# STM32F103VET6.net
KiCad netlist of a schematic drawn in Altium Designer
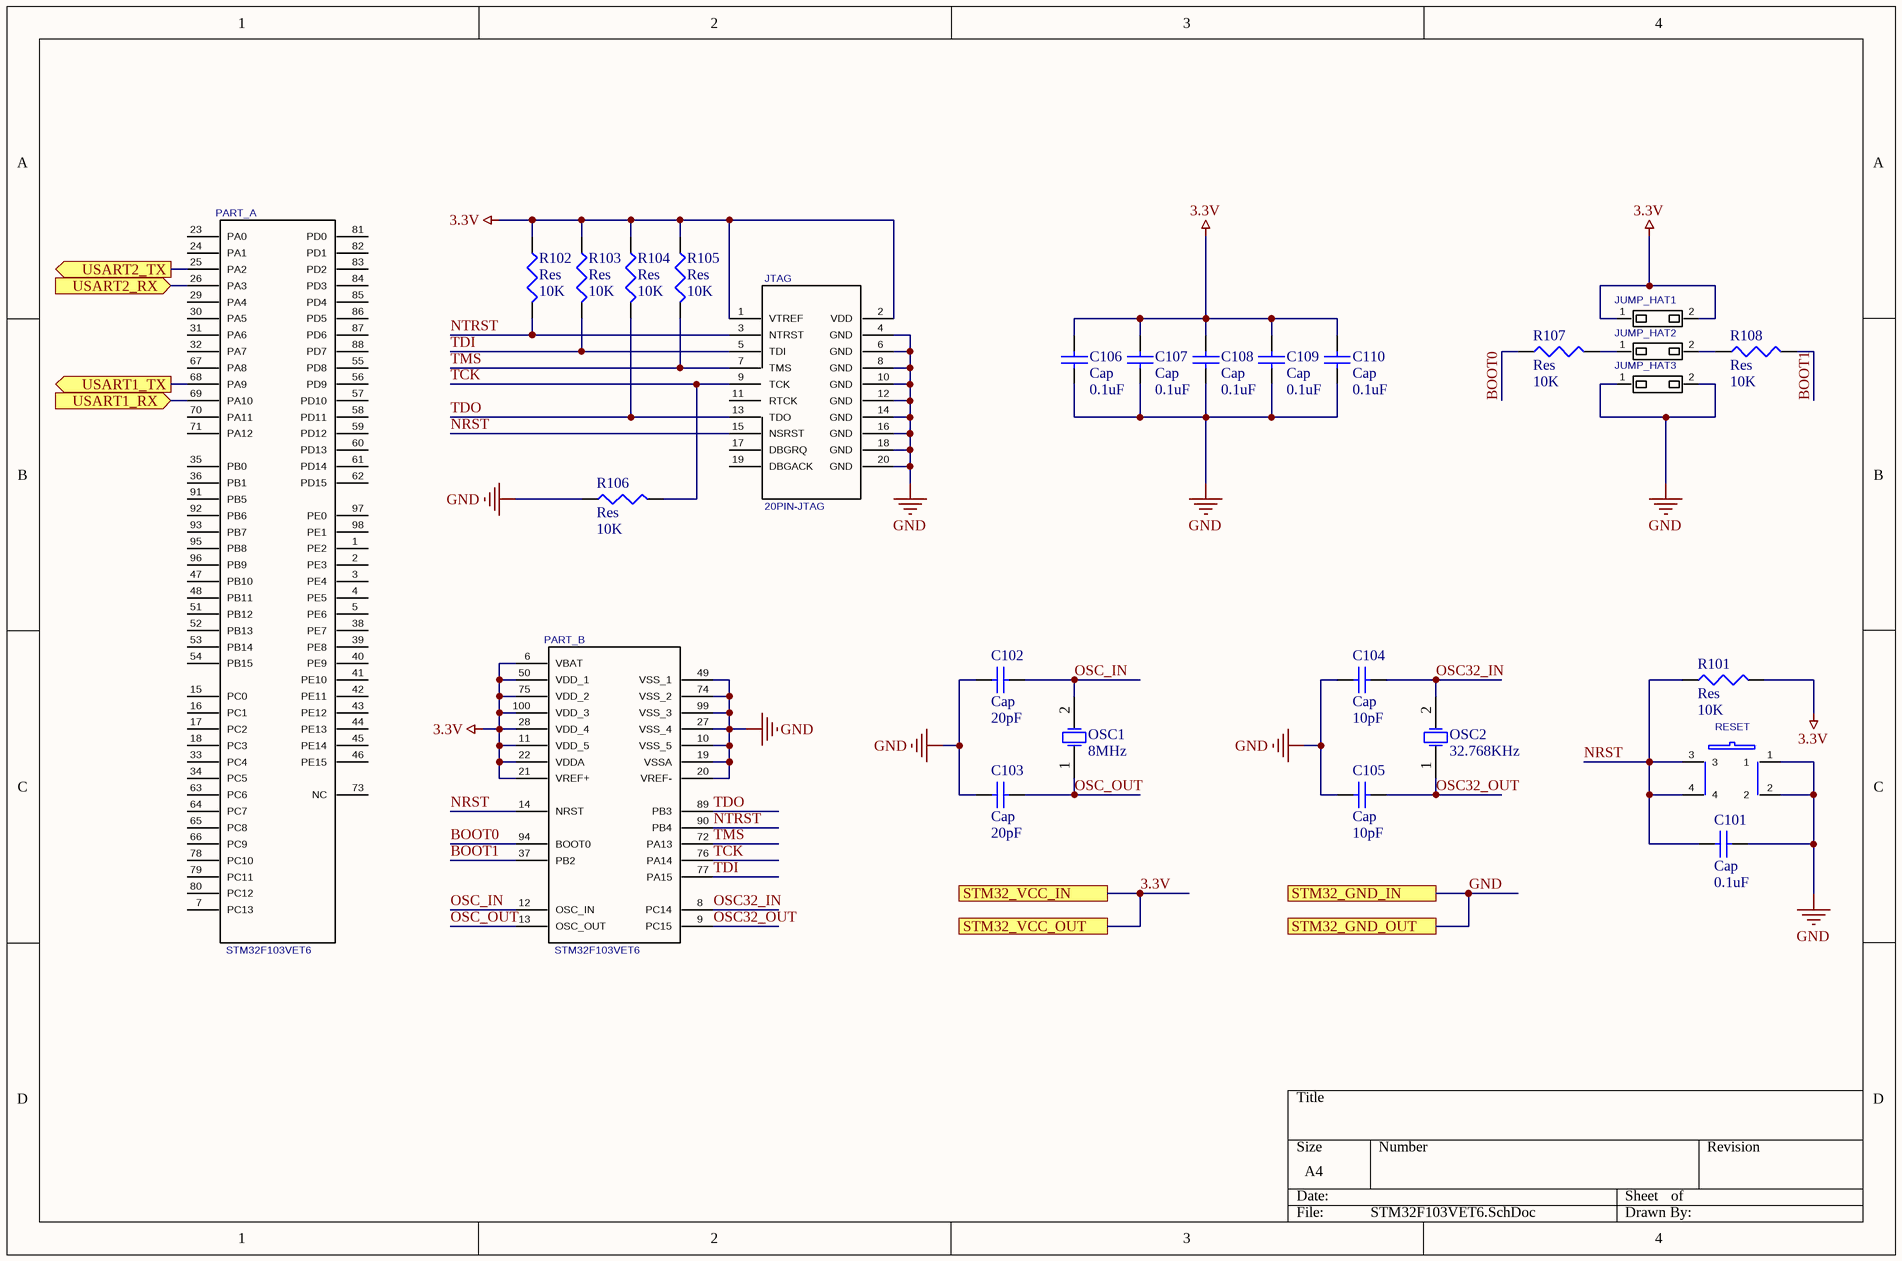
[diagram p0: STM32F103VET6.SchDoc]

(export (version "E")
  (design (tool "Eeschema 10.0.6"))
  (components
    (comp (ref "C101")
      (value "Cap")
      (footprint "RAD-0.3")
      (description "Capacitor")
      (fields (field (name "ALTIUM_VALUE") "0.1uF") (field (name "PUBLISHER") "Altium Limited"))
      (libsource (lib "Miscellaneous Devices") (part "Cap"))
    )
    (comp (ref "C102")
      (value "Cap")
      (footprint "RAD-0.3")
      (description "Capacitor")
      (fields (field (name "ALTIUM_VALUE") "20pF") (field (name "PUBLISHER") "Altium Limited"))
      (libsource (lib "Miscellaneous Devices") (part "Cap"))
    )
    (comp (ref "C103")
      (value "Cap")
      (footprint "RAD-0.3")
      (description "Capacitor")
      (fields (field (name "ALTIUM_VALUE") "20pF") (field (name "PUBLISHER") "Altium Limited"))
      (libsource (lib "Miscellaneous Devices") (part "Cap"))
    )
    (comp (ref "C104")
      (value "Cap")
      (footprint "RAD-0.3")
      (description "Capacitor")
      (fields (field (name "ALTIUM_VALUE") "10pF") (field (name "PUBLISHER") "Altium Limited"))
      (libsource (lib "Miscellaneous Devices") (part "Cap"))
    )
    (comp (ref "C105")
      (value "Cap")
      (footprint "RAD-0.3")
      (description "Capacitor")
      (fields (field (name "ALTIUM_VALUE") "10pF") (field (name "PUBLISHER") "Altium Limited"))
      (libsource (lib "Miscellaneous Devices") (part "Cap"))
    )
    (comp (ref "C106")
      (value "Cap")
      (footprint "RAD-0.3")
      (description "Capacitor")
      (fields (field (name "ALTIUM_VALUE") "0.1uF") (field (name "PUBLISHER") "Altium Limited"))
      (libsource (lib "Miscellaneous Devices") (part "Cap"))
    )
    (comp (ref "C107")
      (value "Cap")
      (footprint "RAD-0.3")
      (description "Capacitor")
      (fields (field (name "ALTIUM_VALUE") "0.1uF") (field (name "PUBLISHER") "Altium Limited"))
      (libsource (lib "Miscellaneous Devices") (part "Cap"))
    )
    (comp (ref "C108")
      (value "Cap")
      (footprint "RAD-0.3")
      (description "Capacitor")
      (fields (field (name "ALTIUM_VALUE") "0.1uF") (field (name "PUBLISHER") "Altium Limited"))
      (libsource (lib "Miscellaneous Devices") (part "Cap"))
    )
    (comp (ref "C109")
      (value "Cap")
      (footprint "RAD-0.3")
      (description "Capacitor")
      (fields (field (name "ALTIUM_VALUE") "0.1uF") (field (name "PUBLISHER") "Altium Limited"))
      (libsource (lib "Miscellaneous Devices") (part "Cap"))
    )
    (comp (ref "C110")
      (value "Cap")
      (footprint "RAD-0.3")
      (description "Capacitor")
      (fields (field (name "ALTIUM_VALUE") "0.1uF") (field (name "PUBLISHER") "Altium Limited"))
      (libsource (lib "Miscellaneous Devices") (part "Cap"))
    )
    (comp (ref "JTAG")
      (value "20PIN-JTAG")
      (footprint "FC20H")
      (description "20pin JTAG")
      (libsource (lib "MINI-V3") (part "20PIN-JTAG"))
    )
    (comp (ref "JUMP_HAT1")
      (value "1X2PIN_SMD")
      (footprint "1X2PIN_SMD")
      (libsource (lib "MINI-V3") (part "1X2PIN_SMD"))
    )
    (comp (ref "JUMP_HAT2")
      (value "1X2PIN_SMD")
      (footprint "1X2PIN_SMD")
      (libsource (lib "MINI-V3") (part "1X2PIN_SMD"))
    )
    (comp (ref "JUMP_HAT3")
      (value "1X2PIN_SMD")
      (footprint "1X2PIN_SMD")
      (libsource (lib "MINI-V3") (part "1X2PIN_SMD"))
    )
    (comp (ref "OSC1")
      (value "8MHz")
      (footprint "R38")
      (description "Crystal Oscillator")
      (fields (field (name "PUBLISHER") "Altium Limited"))
      (libsource (lib "Miscellaneous Devices") (part "XTAL"))
    )
    (comp (ref "OSC2")
      (value "32.768KHz")
      (footprint "R38")
      (description "Crystal Oscillator")
      (fields (field (name "PUBLISHER") "Altium Limited"))
      (libsource (lib "Miscellaneous Devices") (part "XTAL"))
    )
    (comp (ref "PART_")
      (value "STM32F103VET6")
      (footprint "STM32F103VET6-LQFP")
      (libsource (lib "MINI-V3") (part "STM32F103VET6"))
    )
    (comp (ref "R101")
      (value "Res")
      (footprint "J1-0603")
      (description "Resistor")
      (fields (field (name "ALTIUM_VALUE") "10K") (field (name "PUBLISHER") "Altium Limited"))
      (libsource (lib "Miscellaneous Devices") (part "Res3"))
    )
    (comp (ref "R102")
      (value "Res")
      (footprint "J1-0603")
      (description "Resistor")
      (fields (field (name "ALTIUM_VALUE") "10K") (field (name "PUBLISHER") "Altium Limited"))
      (libsource (lib "Miscellaneous Devices") (part "Res3"))
    )
    (comp (ref "R103")
      (value "Res")
      (footprint "J1-0603")
      (description "Resistor")
      (fields (field (name "ALTIUM_VALUE") "10K") (field (name "PUBLISHER") "Altium Limited"))
      (libsource (lib "Miscellaneous Devices") (part "Res3"))
    )
    (comp (ref "R104")
      (value "Res")
      (footprint "J1-0603")
      (description "Resistor")
      (fields (field (name "ALTIUM_VALUE") "10K") (field (name "PUBLISHER") "Altium Limited"))
      (libsource (lib "Miscellaneous Devices") (part "Res3"))
    )
    (comp (ref "R105")
      (value "Res")
      (footprint "J1-0603")
      (description "Resistor")
      (fields (field (name "ALTIUM_VALUE") "10K") (field (name "PUBLISHER") "Altium Limited"))
      (libsource (lib "Miscellaneous Devices") (part "Res3"))
    )
    (comp (ref "R106")
      (value "Res")
      (footprint "J1-0603")
      (description "Resistor")
      (fields (field (name "ALTIUM_VALUE") "10K") (field (name "PUBLISHER") "Altium Limited"))
      (libsource (lib "Miscellaneous Devices") (part "Res3"))
    )
    (comp (ref "R107")
      (value "Res")
      (footprint "J1-0603")
      (description "Resistor")
      (fields (field (name "ALTIUM_VALUE") "10K") (field (name "PUBLISHER") "Altium Limited"))
      (libsource (lib "Miscellaneous Devices") (part "Res3"))
    )
    (comp (ref "R108")
      (value "Res")
      (footprint "J1-0603")
      (description "Resistor")
      (fields (field (name "ALTIUM_VALUE") "10K") (field (name "PUBLISHER") "Altium Limited"))
      (libsource (lib "Miscellaneous Devices") (part "Res3"))
    )
    (comp (ref "RESET") (value "KEY") (footprint "SW6.2/6.2-SMD") (libsource (lib "MINI-V3") (part "KEY")))
  )
  (nets
    (net (code "1") (name "/BOOT0") (class "Default")
      (node (ref "PART_") (pin "94") (pinfunction "BOOT0_94") (pintype "passive"))
      (node (ref "R107") (pin "1") (pinfunction "1_1") (pintype "passive"))
    )
    (net (code "2") (name "/BOOT1") (class "Default")
      (node (ref "PART_") (pin "37") (pinfunction "PB2_37") (pintype "passive"))
      (node (ref "R108") (pin "1") (pinfunction "1_1") (pintype "passive"))
    )
    (net (code "3") (name "/NRST") (class "Default")
      (node (ref "C101") (pin "1") (pinfunction "1_1") (pintype "passive"))
      (node (ref "JTAG") (pin "15") (pinfunction "NSRST_15") (pintype "passive"))
      (node (ref "PART_") (pin "14") (pinfunction "NRST_14") (pintype "passive"))
      (node (ref "R101") (pin "1") (pinfunction "1_1") (pintype "passive"))
      (node (ref "RESET") (pin "3") (pinfunction "3_3") (pintype "passive"))
      (node (ref "RESET") (pin "4") (pinfunction "4_4") (pintype "passive"))
    )
    (net (code "4") (name "/NTRST") (class "Default")
      (node (ref "JTAG") (pin "3") (pinfunction "NTRST_3") (pintype "passive"))
      (node (ref "PART_") (pin "90") (pinfunction "PB4_90") (pintype "passive"))
      (node (ref "R102") (pin "2") (pinfunction "2_2") (pintype "passive"))
    )
    (net (code "5") (name "/OSC32_IN") (class "Default")
      (node (ref "C104") (pin "2") (pinfunction "2_2") (pintype "passive"))
      (node (ref "OSC2") (pin "2") (pinfunction "OSC2_2") (pintype "passive"))
      (node (ref "PART_") (pin "8") (pinfunction "PC14_8") (pintype "passive"))
    )
    (net (code "6") (name "/OSC32_OUT") (class "Default")
      (node (ref "C105") (pin "2") (pinfunction "2_2") (pintype "passive"))
      (node (ref "OSC2") (pin "1") (pinfunction "OSC1_1") (pintype "passive"))
      (node (ref "PART_") (pin "9") (pinfunction "PC15_9") (pintype "passive"))
    )
    (net (code "7") (name "/OSC_IN") (class "Default")
      (node (ref "C102") (pin "2") (pinfunction "2_2") (pintype "passive"))
      (node (ref "OSC1") (pin "2") (pinfunction "OSC2_2") (pintype "passive"))
      (node (ref "PART_") (pin "12") (pinfunction "OSC_IN_12") (pintype "passive"))
    )
    (net (code "8") (name "/OSC_OUT") (class "Default")
      (node (ref "C103") (pin "2") (pinfunction "2_2") (pintype "passive"))
      (node (ref "OSC1") (pin "1") (pinfunction "OSC1_1") (pintype "passive"))
      (node (ref "PART_") (pin "13") (pinfunction "OSC_OUT_13") (pintype "passive"))
    )
    (net (code "9") (name "/TCK") (class "Default")
      (node (ref "JTAG") (pin "9") (pinfunction "TCK_9") (pintype "passive"))
      (node (ref "PART_") (pin "76") (pinfunction "PA14_76") (pintype "passive"))
      (node (ref "R106") (pin "2") (pinfunction "2_2") (pintype "passive"))
    )
    (net (code "10") (name "/TDI") (class "Default")
      (node (ref "JTAG") (pin "5") (pinfunction "TDI_5") (pintype "passive"))
      (node (ref "PART_") (pin "77") (pinfunction "PA15_77") (pintype "passive"))
      (node (ref "R103") (pin "2") (pinfunction "2_2") (pintype "passive"))
    )
    (net (code "11") (name "/TDO") (class "Default")
      (node (ref "JTAG") (pin "13") (pinfunction "TDO_13") (pintype "passive"))
      (node (ref "PART_") (pin "89") (pinfunction "PB3_89") (pintype "passive"))
      (node (ref "R104") (pin "2") (pinfunction "2_2") (pintype "passive"))
    )
    (net (code "12") (name "/TMS") (class "Default")
      (node (ref "JTAG") (pin "7") (pinfunction "TMS_7") (pintype "passive"))
      (node (ref "PART_") (pin "72") (pinfunction "PA13_72") (pintype "passive"))
      (node (ref "R105") (pin "2") (pinfunction "2_2") (pintype "passive"))
    )
    (net (code "13") (name "/USART1_RX") (class "Default")
      (node (ref "PART_") (pin "69") (pinfunction "PA10_69") (pintype "passive"))
    )
    (net (code "14") (name "/USART1_TX") (class "Default")
      (node (ref "PART_") (pin "68") (pinfunction "PA9_68") (pintype "passive"))
    )
    (net (code "15") (name "/USART2_RX") (class "Default")
      (node (ref "PART_") (pin "26") (pinfunction "PA3_26") (pintype "passive"))
    )
    (net (code "16") (name "/USART2_TX") (class "Default")
      (node (ref "PART_") (pin "25") (pinfunction "PA2_25") (pintype "passive"))
    )
    (net (code "17") (name "3.3V") (class "Default")
      (node (ref "C106") (pin "2") (pinfunction "2_2") (pintype "passive"))
      (node (ref "C107") (pin "2") (pinfunction "2_2") (pintype "passive"))
      (node (ref "C108") (pin "2") (pinfunction "2_2") (pintype "passive"))
      (node (ref "C109") (pin "2") (pinfunction "2_2") (pintype "passive"))
      (node (ref "C110") (pin "2") (pinfunction "2_2") (pintype "passive"))
      (node (ref "JTAG") (pin "1") (pinfunction "VTREF_1") (pintype "passive"))
      (node (ref "JTAG") (pin "2") (pinfunction "VDD_2") (pintype "passive"))
      (node (ref "JUMP_HAT1") (pin "1") (pinfunction "1_1") (pintype "passive"))
      (node (ref "JUMP_HAT1") (pin "2") (pinfunction "2_2") (pintype "passive"))
      (node (ref "PART_") (pin "100") (pinfunction "VDD_3_100") (pintype "passive"))
      (node (ref "PART_") (pin "11") (pinfunction "VDD_5_11") (pintype "passive"))
      (node (ref "PART_") (pin "21") (pinfunction "VREF+_21") (pintype "passive"))
      (node (ref "PART_") (pin "22") (pinfunction "VDDA_22") (pintype "passive"))
      (node (ref "PART_") (pin "28") (pinfunction "VDD_4_28") (pintype "passive"))
      (node (ref "PART_") (pin "50") (pinfunction "VDD_1_50") (pintype "passive"))
      (node (ref "PART_") (pin "6") (pinfunction "VBAT_6") (pintype "passive"))
      (node (ref "PART_") (pin "75") (pinfunction "VDD_2_75") (pintype "passive"))
      (node (ref "R101") (pin "2") (pinfunction "2_2") (pintype "passive"))
      (node (ref "R102") (pin "1") (pinfunction "1_1") (pintype "passive"))
      (node (ref "R103") (pin "1") (pinfunction "1_1") (pintype "passive"))
      (node (ref "R104") (pin "1") (pinfunction "1_1") (pintype "passive"))
      (node (ref "R105") (pin "1") (pinfunction "1_1") (pintype "passive"))
    )
    (net (code "18") (name "GND") (class "Default")
      (node (ref "C101") (pin "2") (pinfunction "2_2") (pintype "passive"))
      (node (ref "C102") (pin "1") (pinfunction "1_1") (pintype "passive"))
      (node (ref "C103") (pin "1") (pinfunction "1_1") (pintype "passive"))
      (node (ref "C104") (pin "1") (pinfunction "1_1") (pintype "passive"))
      (node (ref "C105") (pin "1") (pinfunction "1_1") (pintype "passive"))
      (node (ref "C106") (pin "1") (pinfunction "1_1") (pintype "passive"))
      (node (ref "C107") (pin "1") (pinfunction "1_1") (pintype "passive"))
      (node (ref "C108") (pin "1") (pinfunction "1_1") (pintype "passive"))
      (node (ref "C109") (pin "1") (pinfunction "1_1") (pintype "passive"))
      (node (ref "C110") (pin "1") (pinfunction "1_1") (pintype "passive"))
      (node (ref "JTAG") (pin "10") (pinfunction "GND_10") (pintype "passive"))
      (node (ref "JTAG") (pin "12") (pinfunction "GND_12") (pintype "passive"))
      (node (ref "JTAG") (pin "14") (pinfunction "GND_14") (pintype "passive"))
      (node (ref "JTAG") (pin "16") (pinfunction "GND_16") (pintype "passive"))
      (node (ref "JTAG") (pin "18") (pinfunction "GND_18") (pintype "passive"))
      (node (ref "JTAG") (pin "20") (pinfunction "GND_20") (pintype "passive"))
      (node (ref "JTAG") (pin "4") (pinfunction "GND_4") (pintype "passive"))
      (node (ref "JTAG") (pin "6") (pinfunction "GND_6") (pintype "passive"))
      (node (ref "JTAG") (pin "8") (pinfunction "GND_8") (pintype "passive"))
      (node (ref "JUMP_HAT3") (pin "1") (pinfunction "1_1") (pintype "passive"))
      (node (ref "JUMP_HAT3") (pin "2") (pinfunction "2_2") (pintype "passive"))
      (node (ref "PART_") (pin "10") (pinfunction "VSS_5_10") (pintype "passive"))
      (node (ref "PART_") (pin "19") (pinfunction "VSSA_19") (pintype "passive"))
      (node (ref "PART_") (pin "20") (pinfunction "VREF-_20") (pintype "passive"))
      (node (ref "PART_") (pin "27") (pinfunction "VSS_4_27") (pintype "passive"))
      (node (ref "PART_") (pin "49") (pinfunction "VSS_1_49") (pintype "passive"))
      (node (ref "PART_") (pin "74") (pinfunction "VSS_2_74") (pintype "passive"))
      (node (ref "PART_") (pin "99") (pinfunction "VSS_3_99") (pintype "passive"))
      (node (ref "R106") (pin "1") (pinfunction "1_1") (pintype "passive"))
      (node (ref "RESET") (pin "1") (pinfunction "1_1") (pintype "passive"))
      (node (ref "RESET") (pin "2") (pinfunction "2_2") (pintype "passive"))
    )
    (net (code "19") (name "Net-(JUMP_HAT2-Pad1)") (class "Default")
      (node (ref "JUMP_HAT2") (pin "1") (pinfunction "1_1") (pintype "passive"))
      (node (ref "R107") (pin "2") (pinfunction "2_2") (pintype "passive"))
    )
    (net (code "20") (name "Net-(JUMP_HAT2-Pad2)") (class "Default")
      (node (ref "JUMP_HAT2") (pin "2") (pinfunction "2_2") (pintype "passive"))
      (node (ref "R108") (pin "2") (pinfunction "2_2") (pintype "passive"))
    )
    (net (code "21") (name "unconnected-(JTAG-DBGACK-Pad19)") (class "Default")
      (node (ref "JTAG") (pin "19") (pinfunction "DBGACK_19") (pintype "passive"))
    )
    (net (code "22") (name "unconnected-(JTAG-DBGRQ-Pad17)") (class "Default")
      (node (ref "JTAG") (pin "17") (pinfunction "DBGRQ_17") (pintype "passive"))
    )
    (net (code "23") (name "unconnected-(JTAG-RTCK-Pad11)") (class "Default")
      (node (ref "JTAG") (pin "11") (pinfunction "RTCK_11") (pintype "passive"))
    )
    (net (code "24") (name "unconnected-(PART_A-NC-Pad73)") (class "Default")
      (node (ref "PART_") (pin "73") (pinfunction "NC_73") (pintype "passive"))
    )
    (net (code "25") (name "unconnected-(PART_A-PA0-Pad23)") (class "Default")
      (node (ref "PART_") (pin "23") (pinfunction "PA0_23") (pintype "passive"))
    )
    (net (code "26") (name "unconnected-(PART_A-PA1-Pad24)") (class "Default")
      (node (ref "PART_") (pin "24") (pinfunction "PA1_24") (pintype "passive"))
    )
    (net (code "27") (name "unconnected-(PART_A-PA4-Pad29)") (class "Default")
      (node (ref "PART_") (pin "29") (pinfunction "PA4_29") (pintype "passive"))
    )
    (net (code "28") (name "unconnected-(PART_A-PA5-Pad30)") (class "Default")
      (node (ref "PART_") (pin "30") (pinfunction "PA5_30") (pintype "passive"))
    )
    (net (code "29") (name "unconnected-(PART_A-PA6-Pad31)") (class "Default")
      (node (ref "PART_") (pin "31") (pinfunction "PA6_31") (pintype "passive"))
    )
    (net (code "30") (name "unconnected-(PART_A-PA7-Pad32)") (class "Default")
      (node (ref "PART_") (pin "32") (pinfunction "PA7_32") (pintype "passive"))
    )
    (net (code "31") (name "unconnected-(PART_A-PA8-Pad67)") (class "Default")
      (node (ref "PART_") (pin "67") (pinfunction "PA8_67") (pintype "passive"))
    )
    (net (code "32") (name "unconnected-(PART_A-PA11-Pad70)") (class "Default")
      (node (ref "PART_") (pin "70") (pinfunction "PA11_70") (pintype "passive"))
    )
    (net (code "33") (name "unconnected-(PART_A-PA12-Pad71)") (class "Default")
      (node (ref "PART_") (pin "71") (pinfunction "PA12_71") (pintype "passive"))
    )
    (net (code "34") (name "unconnected-(PART_A-PB0-Pad35)") (class "Default")
      (node (ref "PART_") (pin "35") (pinfunction "PB0_35") (pintype "passive"))
    )
    (net (code "35") (name "unconnected-(PART_A-PB1-Pad36)") (class "Default")
      (node (ref "PART_") (pin "36") (pinfunction "PB1_36") (pintype "passive"))
    )
    (net (code "36") (name "unconnected-(PART_A-PB5-Pad91)") (class "Default")
      (node (ref "PART_") (pin "91") (pinfunction "PB5_91") (pintype "passive"))
    )
    (net (code "37") (name "unconnected-(PART_A-PB6-Pad92)") (class "Default")
      (node (ref "PART_") (pin "92") (pinfunction "PB6_92") (pintype "passive"))
    )
    (net (code "38") (name "unconnected-(PART_A-PB7-Pad93)") (class "Default")
      (node (ref "PART_") (pin "93") (pinfunction "PB7_93") (pintype "passive"))
    )
    (net (code "39") (name "unconnected-(PART_A-PB8-Pad95)") (class "Default")
      (node (ref "PART_") (pin "95") (pinfunction "PB8_95") (pintype "passive"))
    )
    (net (code "40") (name "unconnected-(PART_A-PB9-Pad96)") (class "Default")
      (node (ref "PART_") (pin "96") (pinfunction "PB9_96") (pintype "passive"))
    )
    (net (code "41") (name "unconnected-(PART_A-PB10-Pad47)") (class "Default")
      (node (ref "PART_") (pin "47") (pinfunction "PB10_47") (pintype "passive"))
    )
    (net (code "42") (name "unconnected-(PART_A-PB11-Pad48)") (class "Default")
      (node (ref "PART_") (pin "48") (pinfunction "PB11_48") (pintype "passive"))
    )
    (net (code "43") (name "unconnected-(PART_A-PB12-Pad51)") (class "Default")
      (node (ref "PART_") (pin "51") (pinfunction "PB12_51") (pintype "passive"))
    )
    (net (code "44") (name "unconnected-(PART_A-PB13-Pad52)") (class "Default")
      (node (ref "PART_") (pin "52") (pinfunction "PB13_52") (pintype "passive"))
    )
    (net (code "45") (name "unconnected-(PART_A-PB14-Pad53)") (class "Default")
      (node (ref "PART_") (pin "53") (pinfunction "PB14_53") (pintype "passive"))
    )
    (net (code "46") (name "unconnected-(PART_A-PB15-Pad54)") (class "Default")
      (node (ref "PART_") (pin "54") (pinfunction "PB15_54") (pintype "passive"))
    )
    (net (code "47") (name "unconnected-(PART_A-PC0-Pad15)") (class "Default")
      (node (ref "PART_") (pin "15") (pinfunction "PC0_15") (pintype "passive"))
    )
    (net (code "48") (name "unconnected-(PART_A-PC1-Pad16)") (class "Default")
      (node (ref "PART_") (pin "16") (pinfunction "PC1_16") (pintype "passive"))
    )
    (net (code "49") (name "unconnected-(PART_A-PC2-Pad17)") (class "Default")
      (node (ref "PART_") (pin "17") (pinfunction "PC2_17") (pintype "passive"))
    )
    (net (code "50") (name "unconnected-(PART_A-PC3-Pad18)") (class "Default")
      (node (ref "PART_") (pin "18") (pinfunction "PC3_18") (pintype "passive"))
    )
    (net (code "51") (name "unconnected-(PART_A-PC4-Pad33)") (class "Default")
      (node (ref "PART_") (pin "33") (pinfunction "PC4_33") (pintype "passive"))
    )
    (net (code "52") (name "unconnected-(PART_A-PC5-Pad34)") (class "Default")
      (node (ref "PART_") (pin "34") (pinfunction "PC5_34") (pintype "passive"))
    )
    (net (code "53") (name "unconnected-(PART_A-PC6-Pad63)") (class "Default")
      (node (ref "PART_") (pin "63") (pinfunction "PC6_63") (pintype "passive"))
    )
    (net (code "54") (name "unconnected-(PART_A-PC7-Pad64)") (class "Default")
      (node (ref "PART_") (pin "64") (pinfunction "PC7_64") (pintype "passive"))
    )
    (net (code "55") (name "unconnected-(PART_A-PC8-Pad65)") (class "Default")
      (node (ref "PART_") (pin "65") (pinfunction "PC8_65") (pintype "passive"))
    )
    (net (code "56") (name "unconnected-(PART_A-PC9-Pad66)") (class "Default")
      (node (ref "PART_") (pin "66") (pinfunction "PC9_66") (pintype "passive"))
    )
    (net (code "57") (name "unconnected-(PART_A-PC10-Pad78)") (class "Default")
      (node (ref "PART_") (pin "78") (pinfunction "PC10_78") (pintype "passive"))
    )
    (net (code "58") (name "unconnected-(PART_A-PC11-Pad79)") (class "Default")
      (node (ref "PART_") (pin "79") (pinfunction "PC11_79") (pintype "passive"))
    )
    (net (code "59") (name "unconnected-(PART_A-PC12-Pad80)") (class "Default")
      (node (ref "PART_") (pin "80") (pinfunction "PC12_80") (pintype "passive"))
    )
    (net (code "60") (name "unconnected-(PART_A-PC13-Pad7)") (class "Default")
      (node (ref "PART_") (pin "7") (pinfunction "PC13_7") (pintype "passive"))
    )
    (net (code "61") (name "unconnected-(PART_A-PD0-Pad81)") (class "Default")
      (node (ref "PART_") (pin "81") (pinfunction "PD0_81") (pintype "passive"))
    )
    (net (code "62") (name "unconnected-(PART_A-PD1-Pad82)") (class "Default")
      (node (ref "PART_") (pin "82") (pinfunction "PD1_82") (pintype "passive"))
    )
    (net (code "63") (name "unconnected-(PART_A-PD2-Pad83)") (class "Default")
      (node (ref "PART_") (pin "83") (pinfunction "PD2_83") (pintype "passive"))
    )
    (net (code "64") (name "unconnected-(PART_A-PD3-Pad84)") (class "Default")
      (node (ref "PART_") (pin "84") (pinfunction "PD3_84") (pintype "passive"))
    )
    (net (code "65") (name "unconnected-(PART_A-PD4-Pad85)") (class "Default")
      (node (ref "PART_") (pin "85") (pinfunction "PD4_85") (pintype "passive"))
    )
    (net (code "66") (name "unconnected-(PART_A-PD5-Pad86)") (class "Default")
      (node (ref "PART_") (pin "86") (pinfunction "PD5_86") (pintype "passive"))
    )
    (net (code "67") (name "unconnected-(PART_A-PD6-Pad87)") (class "Default")
      (node (ref "PART_") (pin "87") (pinfunction "PD6_87") (pintype "passive"))
    )
    (net (code "68") (name "unconnected-(PART_A-PD7-Pad88)") (class "Default")
      (node (ref "PART_") (pin "88") (pinfunction "PD7_88") (pintype "passive"))
    )
    (net (code "69") (name "unconnected-(PART_A-PD8-Pad55)") (class "Default")
      (node (ref "PART_") (pin "55") (pinfunction "PD8_55") (pintype "passive"))
    )
    (net (code "70") (name "unconnected-(PART_A-PD9-Pad56)") (class "Default")
      (node (ref "PART_") (pin "56") (pinfunction "PD9_56") (pintype "passive"))
    )
    (net (code "71") (name "unconnected-(PART_A-PD10-Pad57)") (class "Default")
      (node (ref "PART_") (pin "57") (pinfunction "PD10_57") (pintype "passive"))
    )
    (net (code "72") (name "unconnected-(PART_A-PD11-Pad58)") (class "Default")
      (node (ref "PART_") (pin "58") (pinfunction "PD11_58") (pintype "passive"))
    )
    (net (code "73") (name "unconnected-(PART_A-PD12-Pad59)") (class "Default")
      (node (ref "PART_") (pin "59") (pinfunction "PD12_59") (pintype "passive"))
    )
    (net (code "74") (name "unconnected-(PART_A-PD13-Pad60)") (class "Default")
      (node (ref "PART_") (pin "60") (pinfunction "PD13_60") (pintype "passive"))
    )
    (net (code "75") (name "unconnected-(PART_A-PD14-Pad61)") (class "Default")
      (node (ref "PART_") (pin "61") (pinfunction "PD14_61") (pintype "passive"))
    )
    (net (code "76") (name "unconnected-(PART_A-PD15-Pad62)") (class "Default")
      (node (ref "PART_") (pin "62") (pinfunction "PD15_62") (pintype "passive"))
    )
    (net (code "77") (name "unconnected-(PART_A-PE0-Pad97)") (class "Default")
      (node (ref "PART_") (pin "97") (pinfunction "PE0_97") (pintype "passive"))
    )
    (net (code "78") (name "unconnected-(PART_A-PE1-Pad98)") (class "Default")
      (node (ref "PART_") (pin "98") (pinfunction "PE1_98") (pintype "passive"))
    )
    (net (code "79") (name "unconnected-(PART_A-PE2-Pad1)") (class "Default")
      (node (ref "PART_") (pin "1") (pinfunction "PE2_1") (pintype "passive"))
    )
    (net (code "80") (name "unconnected-(PART_A-PE3-Pad2)") (class "Default")
      (node (ref "PART_") (pin "2") (pinfunction "PE3_2") (pintype "passive"))
    )
    (net (code "81") (name "unconnected-(PART_A-PE4-Pad3)") (class "Default")
      (node (ref "PART_") (pin "3") (pinfunction "PE4_3") (pintype "passive"))
    )
    (net (code "82") (name "unconnected-(PART_A-PE5-Pad4)") (class "Default")
      (node (ref "PART_") (pin "4") (pinfunction "PE5_4") (pintype "passive"))
    )
    (net (code "83") (name "unconnected-(PART_A-PE6-Pad5)") (class "Default")
      (node (ref "PART_") (pin "5") (pinfunction "PE6_5") (pintype "passive"))
    )
    (net (code "84") (name "unconnected-(PART_A-PE7-Pad38)") (class "Default")
      (node (ref "PART_") (pin "38") (pinfunction "PE7_38") (pintype "passive"))
    )
    (net (code "85") (name "unconnected-(PART_A-PE8-Pad39)") (class "Default")
      (node (ref "PART_") (pin "39") (pinfunction "PE8_39") (pintype "passive"))
    )
    (net (code "86") (name "unconnected-(PART_A-PE9-Pad40)") (class "Default")
      (node (ref "PART_") (pin "40") (pinfunction "PE9_40") (pintype "passive"))
    )
    (net (code "87") (name "unconnected-(PART_A-PE10-Pad41)") (class "Default")
      (node (ref "PART_") (pin "41") (pinfunction "PE10_41") (pintype "passive"))
    )
    (net (code "88") (name "unconnected-(PART_A-PE11-Pad42)") (class "Default")
      (node (ref "PART_") (pin "42") (pinfunction "PE11_42") (pintype "passive"))
    )
    (net (code "89") (name "unconnected-(PART_A-PE12-Pad43)") (class "Default")
      (node (ref "PART_") (pin "43") (pinfunction "PE12_43") (pintype "passive"))
    )
    (net (code "90") (name "unconnected-(PART_A-PE13-Pad44)") (class "Default")
      (node (ref "PART_") (pin "44") (pinfunction "PE13_44") (pintype "passive"))
    )
    (net (code "91") (name "unconnected-(PART_A-PE14-Pad45)") (class "Default")
      (node (ref "PART_") (pin "45") (pinfunction "PE14_45") (pintype "passive"))
    )
    (net (code "92") (name "unconnected-(PART_A-PE15-Pad46)") (class "Default")
      (node (ref "PART_") (pin "46") (pinfunction "PE15_46") (pintype "passive"))
    )
  )
)
